# oak_pcb.net
KiCad netlist of a schematic drawn in EAGLE
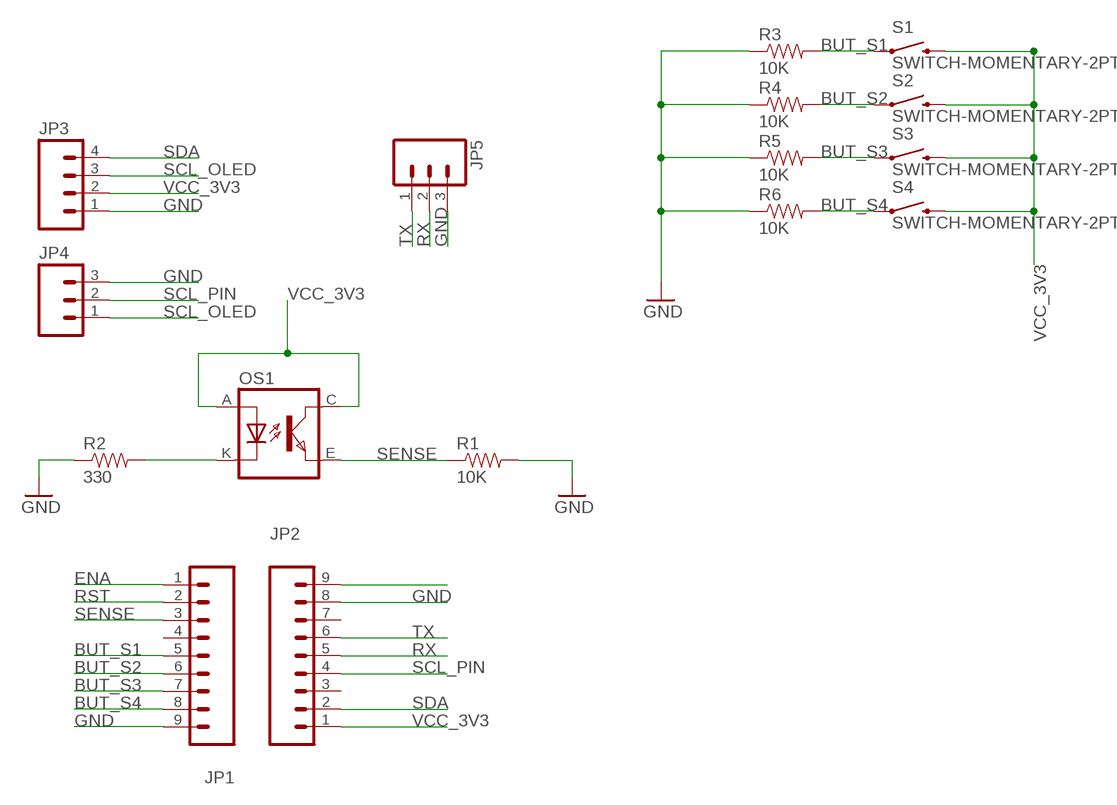
[diagram p0: schematic, sheet 1]

(export (version "E")
  (design (tool "Eeschema 10.0.6"))
  (components
    (comp (ref "JP1")
      (value "M09LOCK")
      (footprint "eagle-import:1X09_LOCK")
      (libsource (lib "eagle-import") (part "M09LOCK"))
    )
    (comp (ref "JP2")
      (value "M09LOCK")
      (footprint "eagle-import:1X09_LOCK")
      (libsource (lib "eagle-import") (part "M09LOCK"))
    )
    (comp (ref "JP3")
      (value "M04LOCK")
      (footprint "eagle-import:1X04_LOCK")
      (libsource (lib "eagle-import") (part "M04LOCK"))
    )
    (comp (ref "JP4")
      (value "M03LOCK")
      (footprint "eagle-import:1X03_LOCK")
      (libsource (lib "eagle-import") (part "M03LOCK"))
    )
    (comp (ref "JP5")
      (value "M03LOCK")
      (footprint "eagle-import:1X03_LOCK")
      (libsource (lib "eagle-import") (part "M03LOCK"))
    )
    (comp (ref "OS1")
      (value "TCRT5000")
      (footprint "eagle-import:TCRT5000")
      (libsource (lib "eagle-import") (part "TCRT5000"))
    )
    (comp (ref "R1")
      (value "10K")
      (footprint "eagle-import:AXIAL-0.4")
      (libsource (lib "eagle-import") (part "RESISTORPTH-1/4W"))
    )
    (comp (ref "R2")
      (value "330")
      (footprint "eagle-import:AXIAL-0.4")
      (libsource (lib "eagle-import") (part "RESISTORPTH-1/4W"))
    )
    (comp (ref "R3")
      (value "10K")
      (footprint "eagle-import:AXIAL-0.4")
      (libsource (lib "eagle-import") (part "RESISTORPTH-1/4W"))
    )
    (comp (ref "R4")
      (value "10K")
      (footprint "eagle-import:AXIAL-0.4")
      (libsource (lib "eagle-import") (part "RESISTORPTH-1/4W"))
    )
    (comp (ref "R5")
      (value "10K")
      (footprint "eagle-import:AXIAL-0.4")
      (libsource (lib "eagle-import") (part "RESISTORPTH-1/4W"))
    )
    (comp (ref "R6")
      (value "10K")
      (footprint "eagle-import:AXIAL-0.4")
      (libsource (lib "eagle-import") (part "RESISTORPTH-1/4W"))
    )
    (comp (ref "S1")
      (value "SWITCH-MOMENTARY-2PTH")
      (footprint "eagle-import:TACTILE-PTH")
      (libsource (lib "eagle-import") (part "SWITCH-MOMENTARY-2PTH"))
    )
    (comp (ref "S2")
      (value "SWITCH-MOMENTARY-2PTH")
      (footprint "eagle-import:TACTILE-PTH")
      (libsource (lib "eagle-import") (part "SWITCH-MOMENTARY-2PTH"))
    )
    (comp (ref "S3")
      (value "SWITCH-MOMENTARY-2PTH")
      (footprint "eagle-import:TACTILE-PTH")
      (libsource (lib "eagle-import") (part "SWITCH-MOMENTARY-2PTH"))
    )
    (comp (ref "S4")
      (value "SWITCH-MOMENTARY-2PTH")
      (footprint "eagle-import:TACTILE-PTH")
      (libsource (lib "eagle-import") (part "SWITCH-MOMENTARY-2PTH"))
    )
  )
  (nets
    (net (code "1") (name "/BUT_S1") (class "Default")
      (node (ref "JP1") (pin "5") (pinfunction "5_5") (pintype "passive"))
      (node (ref "R3") (pin "P$2") (pinfunction "2_P$2") (pintype "passive"))
      (node (ref "S1") (pin "1") (pinfunction "1_1") (pintype "passive"))
    )
    (net (code "2") (name "/BUT_S2") (class "Default")
      (node (ref "JP1") (pin "6") (pinfunction "6_6") (pintype "passive"))
      (node (ref "R4") (pin "P$2") (pinfunction "2_P$2") (pintype "passive"))
      (node (ref "S2") (pin "1") (pinfunction "1_1") (pintype "passive"))
    )
    (net (code "3") (name "/BUT_S3") (class "Default")
      (node (ref "JP1") (pin "7") (pinfunction "7_7") (pintype "passive"))
      (node (ref "R5") (pin "P$2") (pinfunction "2_P$2") (pintype "passive"))
      (node (ref "S3") (pin "1") (pinfunction "1_1") (pintype "passive"))
    )
    (net (code "4") (name "/BUT_S4") (class "Default")
      (node (ref "JP1") (pin "8") (pinfunction "8_8") (pintype "passive"))
      (node (ref "R6") (pin "P$2") (pinfunction "2_P$2") (pintype "passive"))
      (node (ref "S4") (pin "1") (pinfunction "1_1") (pintype "passive"))
    )
    (net (code "5") (name "/ENA") (class "Default")
      (node (ref "JP1") (pin "1") (pinfunction "1_1") (pintype "passive"))
    )
    (net (code "6") (name "/RST") (class "Default")
      (node (ref "JP1") (pin "2") (pinfunction "2_2") (pintype "passive"))
    )
    (net (code "7") (name "/RX") (class "Default")
      (node (ref "JP2") (pin "5") (pinfunction "5_5") (pintype "passive"))
      (node (ref "JP5") (pin "2") (pinfunction "2_2") (pintype "passive"))
    )
    (net (code "8") (name "/SCL_OLED") (class "Default")
      (node (ref "JP3") (pin "3") (pinfunction "3_3") (pintype "passive"))
      (node (ref "JP4") (pin "1") (pinfunction "1_1") (pintype "passive"))
    )
    (net (code "9") (name "/SCL_PIN") (class "Default")
      (node (ref "JP2") (pin "4") (pinfunction "4_4") (pintype "passive"))
      (node (ref "JP4") (pin "2") (pinfunction "2_2") (pintype "passive"))
    )
    (net (code "10") (name "/SDA") (class "Default")
      (node (ref "JP2") (pin "2") (pinfunction "2_2") (pintype "passive"))
      (node (ref "JP3") (pin "4") (pinfunction "4_4") (pintype "passive"))
    )
    (net (code "11") (name "/SENSE") (class "Default")
      (node (ref "JP1") (pin "3") (pinfunction "3_3") (pintype "passive"))
      (node (ref "OS1") (pin "E") (pinfunction "EMITTER_E") (pintype "passive"))
      (node (ref "R1") (pin "P$1") (pinfunction "1_P$1") (pintype "passive"))
    )
    (net (code "12") (name "/TX") (class "Default")
      (node (ref "JP2") (pin "6") (pinfunction "6_6") (pintype "passive"))
      (node (ref "JP5") (pin "1") (pinfunction "1_1") (pintype "passive"))
    )
    (net (code "13") (name "/VCC_3V3") (class "Default")
      (node (ref "JP2") (pin "1") (pinfunction "1_1") (pintype "passive"))
      (node (ref "JP3") (pin "2") (pinfunction "2_2") (pintype "passive"))
      (node (ref "OS1") (pin "A") (pinfunction "ANODE_A") (pintype "passive"))
      (node (ref "OS1") (pin "C") (pinfunction "COLLECTOR_C") (pintype "passive"))
      (node (ref "S1") (pin "3") (pinfunction "2_3") (pintype "passive"))
      (node (ref "S2") (pin "3") (pinfunction "2_3") (pintype "passive"))
      (node (ref "S3") (pin "3") (pinfunction "2_3") (pintype "passive"))
      (node (ref "S4") (pin "3") (pinfunction "2_3") (pintype "passive"))
    )
    (net (code "14") (name "GND") (class "Default")
      (node (ref "JP1") (pin "9") (pinfunction "9_9") (pintype "passive"))
      (node (ref "JP2") (pin "8") (pinfunction "8_8") (pintype "passive"))
      (node (ref "JP3") (pin "1") (pinfunction "1_1") (pintype "passive"))
      (node (ref "JP4") (pin "3") (pinfunction "3_3") (pintype "passive"))
      (node (ref "JP5") (pin "3") (pinfunction "3_3") (pintype "passive"))
      (node (ref "R1") (pin "P$2") (pinfunction "2_P$2") (pintype "passive"))
      (node (ref "R2") (pin "P$1") (pinfunction "1_P$1") (pintype "passive"))
      (node (ref "R3") (pin "P$1") (pinfunction "1_P$1") (pintype "passive"))
      (node (ref "R4") (pin "P$1") (pinfunction "1_P$1") (pintype "passive"))
      (node (ref "R5") (pin "P$1") (pinfunction "1_P$1") (pintype "passive"))
      (node (ref "R6") (pin "P$1") (pinfunction "1_P$1") (pintype "passive"))
    )
    (net (code "15") (name "Net-(OS1-CATHODE)") (class "Default")
      (node (ref "OS1") (pin "K") (pinfunction "CATHODE_K") (pintype "passive"))
      (node (ref "R2") (pin "P$2") (pinfunction "2_P$2") (pintype "passive"))
    )
    (net (code "16") (name "unconnected-(JP1-Pad4)") (class "Default")
      (node (ref "JP1") (pin "4") (pinfunction "4_4") (pintype "passive"))
    )
    (net (code "17") (name "unconnected-(JP2-Pad3)") (class "Default")
      (node (ref "JP2") (pin "3") (pinfunction "3_3") (pintype "passive"))
    )
    (net (code "18") (name "unconnected-(JP2-Pad7)") (class "Default")
      (node (ref "JP2") (pin "7") (pinfunction "7_7") (pintype "passive"))
    )
    (net (code "19") (name "unconnected-(JP2-Pad9)") (class "Default")
      (node (ref "JP2") (pin "9") (pinfunction "9_9") (pintype "passive"))
    )
  )
)
